# DM1092_Battery_Alarm.net
KiCad netlist of a schematic drawn in Altium Designer
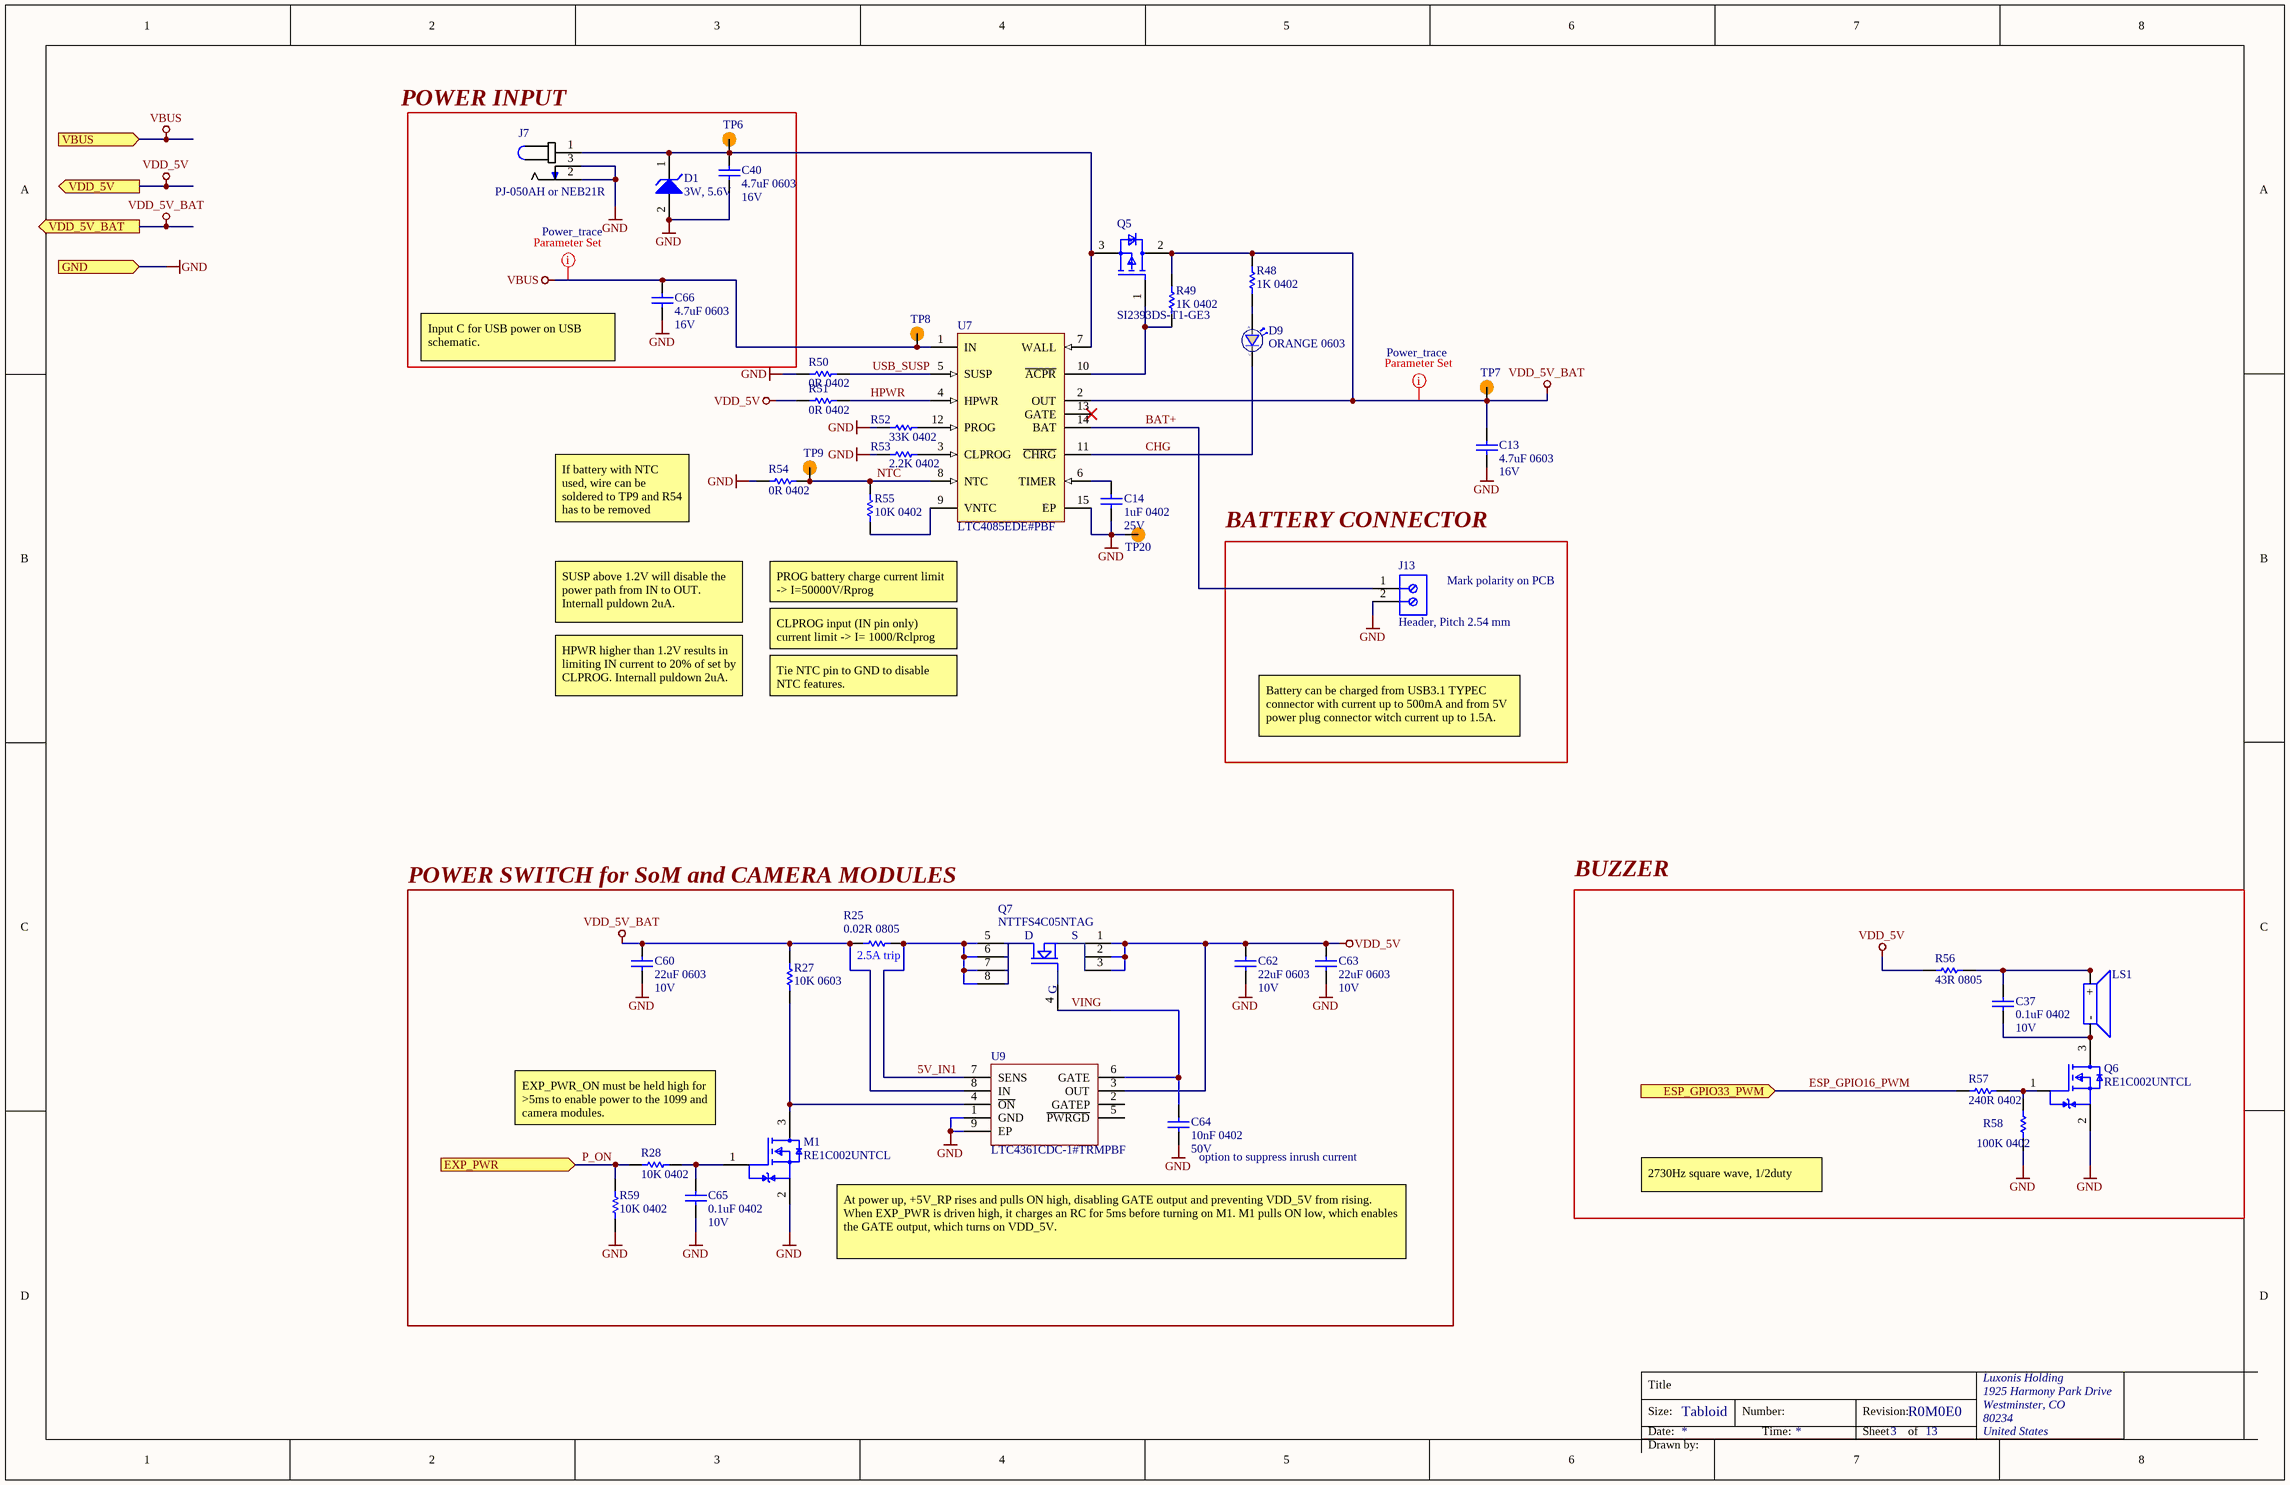
[diagram p0: DM1092_Battery&Alarm.SchDoc]

(export (version "E")
  (design (tool "Eeschema 10.0.6"))
  (components
    (comp (ref "C13")
      (value "4.7uF 0603")
      (footprint "CAP_Altium_Vault_Generic:CAPC0603(1608)100_N")
      (description "CAP CER 4.7UF 16V X5R 0603 10%")
      (fields (field (name "TOLERANCE") "10%") (field (name "VOLTAGE RATING") "16V"))
      (libsource (lib "LuxonisMaster") (part "GRM188R61C475KAAJD"))
    )
    (comp (ref "C14")
      (value "1uF 0402")
      (footprint "CAP_Altium_Vault_Generic:CAPC0402(1005)70_N")
      (description "CAP CER 1UF 25V X5R 0402 10%")
      (fields
        (field (name "TOLERANCE") "10%")
        (field (name "VOLTAGE") "25V")
        (field (name "VOLTAGE RATING") "25V")
      )
      (libsource (lib "LuxonisMaster") (part "GRM155R61E105KA12D"))
    )
    (comp (ref "C37")
      (value "0.1uF 0402")
      (footprint "CAP_Altium_Vault_Generic:CAPC0402(1005)70_N")
      (description "CAP CER 0.1UF 10V X7R 0402 5%")
      (fields (field (name "TOLERANCE") "5%") (field (name "VOLTAGE RATING") "10V"))
      (libsource (lib "LuxonisMaster") (part "GRM155R71A104JA01D"))
    )
    (comp (ref "C40")
      (value "4.7uF 0603")
      (footprint "CAP_Altium_Vault_Generic:CAPC0603(1608)100_N")
      (description "CAP CER 4.7UF 16V X5R 0603 10%")
      (fields (field (name "TOLERANCE") "10%") (field (name "VOLTAGE RATING") "16V"))
      (libsource (lib "LuxonisMaster") (part "GRM188R61C475KAAJD"))
    )
    (comp (ref "C60")
      (value "22uF 0603")
      (footprint "CAP_Altium_Vault_Generic:CAPC0603(1608)100_N")
      (description "CAP CER 22UF 10V X5R 0603 20%")
      (fields (field (name "VOLTAGE RATING") "10V") (field (name "TOLERANCE") "20%"))
      (libsource (lib "LuxonisMaster") (part "GRM188R61A226ME15D"))
    )
    (comp (ref "C62")
      (value "22uF 0603")
      (footprint "CAP_Altium_Vault_Generic:CAPC0603(1608)100_N")
      (description "CAP CER 22UF 10V X5R 0603 20%")
      (fields (field (name "VOLTAGE RATING") "10V") (field (name "TOLERANCE") "20%"))
      (libsource (lib "LuxonisMaster") (part "GRM188R61A226ME15D"))
    )
    (comp (ref "C63")
      (value "22uF 0603")
      (footprint "CAP_Altium_Vault_Generic:CAPC0603(1608)100_N")
      (description "CAP CER 22UF 10V X5R 0603 20%")
      (fields (field (name "VOLTAGE RATING") "10V") (field (name "TOLERANCE") "20%"))
      (libsource (lib "LuxonisMaster") (part "GRM188R61A226ME15D"))
    )
    (comp (ref "C64")
      (value "10nF 0402")
      (footprint "CAP_Altium_Vault_Generic:CAPC0402(1005)60_N")
      (description "CAP CER 10000PF 50V X7R 0402")
      (fields
        (field (name "TOLERANCE") "10%")
        (field (name "VOLTAGE") "25V")
        (field (name "VOLTAGE RATING") "50V")
      )
      (libsource (lib "LuxonisMaster") (part "GRM155R71H103KA88D"))
    )
    (comp (ref "C65")
      (value "0.1uF 0402")
      (footprint "CAP_Altium_Vault_Generic:CAPC0402(1005)70_N")
      (description "CAP CER 0.1UF 10V X7R 0402 5%")
      (fields (field (name "TOLERANCE") "5%") (field (name "VOLTAGE RATING") "10V"))
      (libsource (lib "LuxonisMaster") (part "GRM155R71A104JA01D"))
    )
    (comp (ref "C66")
      (value "4.7uF 0603")
      (footprint "CAP_Altium_Vault_Generic:CAPC0603(1608)100_N")
      (description "CAP CER 4.7UF 16V X5R 0603 10%")
      (fields (field (name "TOLERANCE") "10%") (field (name "VOLTAGE RATING") "16V"))
      (libsource (lib "LuxonisMaster") (part "GRM188R61C475KAAJD"))
    )
    (comp (ref "D1")
      (value "3W, 5.6V")
      (footprint "DM1092_R0M0E0:1SMB5919BT3G")
      (description "DIODE ZENER 5.6V 3W SMB")
      (fields (field (name "TOLERANCE") "5%"))
      (libsource (lib "DM1092_R0M0E0") (part "1SMB5919BT3G"))
    )
    (comp (ref "D9")
      (value "ORANGE 0603")
      (footprint "LuxonisMaster:SML_D1xx8W")
      (description "LED ORANGE DIFFUSED 0603 SMD Orange 605nm LED Indication - Discrete 2.2V 0603 (1608 Metric)")
      (libsource (lib "LuxonisMaster") (part "SML-D12D8WT86"))
    )
    (comp (ref "J7")
      (value "PJ-050AH or NEB21R")
      (footprint "LuxonisMaster:PJ-050AH/NEB21R_COMBO")
      (description "CONN POWER PIN 2 POS RA PTH Barrel jack 2.1mm x 5.5mm combo footprint")
      (libsource (lib "LuxonisMaster") (part "PJ-050AH/NEB21R_COMBO"))
    )
    (comp (ref "J13")
      (value "Header, Pitch 2.54 mm")
      (footprint "PHOE-1725656-2")
      (fields
        (field (name "MANUFACTURER PART NO.") "1725656")
        (field (name "MANUFACTURER") "Phoenix Contact")
        (field (name "VOLTAGE") "125V")
      )
      (libsource (lib "DM1092_R0M0E0") (part "1725656"))
    )
    (comp (ref "LS1")
      (value "KSSGJ4B20")
      (footprint "KSSGJ4B20")
      (description "KINGSTATE - KSSGJ4B20 - MAGNETIC TRANSDUCER, SMD TYPE")
      (libsource (lib "DM1092_R0M0E0") (part "KSSGJ4B20"))
    )
    (comp (ref "M1")
      (value "RE1C002UNTCL")
      (footprint "LuxonisMaster:RE1C002UNTCL")
      (description "MOSFET N-CH 20V 0.2A EMT3")
      (libsource (lib "LuxonisMaster") (part "RE1C002UNTCL"))
    )
    (comp (ref "Q5")
      (value "SI2393DS-T1-GE3")
      (footprint "FP-S-03946-MFG")
      (description "MOSFET P-CH 30V 7.5A SOT23-3")
      (fields
        (field (name "MANUFACTURER") "Vishay Siliconix")
        (field (name "MANUFACTURER PART NUMBER") "SI2307CDS-T1-GE3")
      )
      (libsource (lib "DM1092_R0M0E0") (part "SI2393DS-T1-GE3"))
    )
    (comp (ref "Q6")
      (value "RE1C002UNTCL")
      (footprint "LuxonisMaster:RE1C002UNTCL")
      (description "MOSFET N-CH 20V 0.2A EMT3")
      (libsource (lib "LuxonisMaster") (part "RE1C002UNTCL"))
    )
    (comp (ref "Q7")
      (value "NTTFS4C05NTAG")
      (footprint "LuxonisMaster:NTTFS4C05NTAG")
      (description "MOSFET N-CH 30V 75A U8FL")
      (libsource (lib "LuxonisMaster") (part "NTTFS4C05NTAG"))
    )
    (comp (ref "R25")
      (value "0.02R 0805")
      (footprint "RES_Altium_Vault_Generic:RESC0805(2012)_N")
      (description "RES 0.02 OHM 1% 1/2W 0805")
      (fields (field (name "TOLERANCE") "1%"))
      (libsource (lib "LuxonisMaster") (part "ERJ-6BWFR020V"))
    )
    (comp (ref "R27")
      (value "10K 0603")
      (footprint "RES_Altium_Vault_Generic:RESC0603(1608)_N")
      (description "RES SMD 10K OHM 1% 1/10W 0603")
      (fields (field (name "TOLERANCE") "1%"))
      (libsource (lib "LuxonisMaster") (part "RC0603FR-0710KL"))
    )
    (comp (ref "R28")
      (value "10K 0402")
      (footprint "RES_Altium_Vault_Generic:RESC0402(1005)_L")
      (fields (field (name "TOLERANCE") "1%"))
      (libsource (lib "LuxonisMaster") (part "RC0402FR-1310KL"))
    )
    (comp (ref "R48")
      (value "1K 0402")
      (footprint "RES_Altium_Vault_Generic:RESC0402(1005)_N")
      (fields (field (name "TOLERANCE") "1%"))
      (libsource (lib "LuxonisMaster") (part "RC0402FR-071KL"))
    )
    (comp (ref "R49")
      (value "1K 0402")
      (footprint "RES_Altium_Vault_Generic:RESC0402(1005)_N")
      (fields (field (name "TOLERANCE") "1%"))
      (libsource (lib "LuxonisMaster") (part "RC0402FR-071KL"))
    )
    (comp (ref "R50")
      (value "0R 0402")
      (footprint "RES_Altium_Vault_Generic:RESC0402(1005)_L")
      (description "RES SMD 0 OHM JUMPER 1/16W 0402")
      (fields (field (name "TOLERANCE") "5%"))
      (libsource (lib "LuxonisMaster") (part "CRCW04020000Z0ED"))
    )
    (comp (ref "R51")
      (value "0R 0402")
      (footprint "RES_Altium_Vault_Generic:RESC0402(1005)_L")
      (description "RES SMD 0 OHM JUMPER 1/16W 0402")
      (fields (field (name "TOLERANCE") "5%"))
      (libsource (lib "LuxonisMaster") (part "CRCW04020000Z0ED"))
    )
    (comp (ref "R52")
      (value "33K 0402")
      (footprint "RES_Altium_Vault_Generic:RESC0402(1005)_L")
      (description "RES SMD 33K OHM 1% 1/16W 0402")
      (fields (field (name "TOLERANCE") "1%"))
      (libsource (lib "LuxonisMaster") (part "CRCW040233K0FKED"))
    )
    (comp (ref "R53")
      (value "2.2K 0402")
      (footprint "RES_Altium_Vault_Generic:RESC0402(1005)_N")
      (description "RES SMD 2.2K OHM 1% 1/16W 0402")
      (fields (field (name "TOLERANCE") "1%"))
      (libsource (lib "LuxonisMaster") (part "RC0402FR-072K2L"))
    )
    (comp (ref "R54")
      (value "0R 0402")
      (footprint "RES_Altium_Vault_Generic:RESC0402(1005)_L")
      (description "RES SMD 0 OHM JUMPER 1/16W 0402")
      (fields (field (name "TOLERANCE") "5%"))
      (libsource (lib "LuxonisMaster") (part "CRCW04020000Z0ED"))
    )
    (comp (ref "R55")
      (value "10K 0402")
      (footprint "RES_Altium_Vault_Generic:RESC0402(1005)_N")
      (fields (field (name "TOLERANCE") "1%"))
      (libsource (lib "LuxonisMaster") (part "RC0402FR-1310KL"))
    )
    (comp (ref "R56")
      (value "43R 0805")
      (footprint "RESC0805(2012)_N")
      (description "RES SMD 43 OHM 5% 1/8W 0805")
      (fields
        (field (name "MANUFACTURER") "Yageo")
        (field (name "MANUFACTURER PART NUMBER") "RC0805JR-0743RL")
      )
      (libsource (lib "LuxonisMaster") (part "RC0805JR-0743RL"))
    )
    (comp (ref "R57")
      (value "240R 0402")
      (footprint "RES_Altium_Vault_Generic:RESC0402(1005)_N")
      (description "RES SMD 240 OHM 1% 1/16W 0402")
      (fields (field (name "TOLERANCE") "1%"))
      (libsource (lib "LuxonisMaster") (part "RC0402FR-07240RL"))
    )
    (comp (ref "R58")
      (value "100K 0402")
      (footprint "RES_Altium_Vault_Generic:RESC0402(1005)_L")
      (description "RES SMD 100K OHM 1% 1/16W 0402")
      (fields (field (name "TOLERANCE") "1%"))
      (libsource (lib "LuxonisMaster") (part "RC0402FR-07100KL"))
    )
    (comp (ref "R59")
      (value "10K 0402")
      (footprint "RES_Altium_Vault_Generic:RESC0402(1005)_L")
      (fields (field (name "TOLERANCE") "1%"))
      (libsource (lib "LuxonisMaster") (part "RC0402FR-1310KL"))
    )
    (comp (ref "TP6")
      (value "TP100_200_NS")
      (footprint "LuxonisMaster:TP100_200_NS")
      (libsource (lib "LuxonisMaster") (part "TEST_POINT"))
    )
    (comp (ref "TP7")
      (value "TP100_200_NS")
      (footprint "LuxonisMaster:TP100_200_NS")
      (libsource (lib "LuxonisMaster") (part "TEST_POINT"))
    )
    (comp (ref "TP8")
      (value "TP100_200_NS")
      (footprint "LuxonisMaster:TP100_200_NS")
      (libsource (lib "LuxonisMaster") (part "TEST_POINT"))
    )
    (comp (ref "TP9")
      (value "TP100_200_NS")
      (footprint "LuxonisMaster:TP100_200_NS")
      (libsource (lib "LuxonisMaster") (part "TEST_POINT"))
    )
    (comp (ref "TP20")
      (value "TP100_200_NS")
      (footprint "LuxonisMaster:TP100_200_NS")
      (libsource (lib "LuxonisMaster") (part "TEST_POINT"))
    )
    (comp (ref "U7")
      (value "LTC4085EDE#PBF")
      (footprint "LT-DE-14_V")
      (fields (field (name "MANUFACTURER") "Linear Technology"))
      (libsource (lib "DM1092_R0M0E0") (part "LTC4085EDE#PBF"))
    )
    (comp (ref "U9")
      (value "LTC4361CDC-1#TRMPBF")
      (footprint "LuxonisMaster:LTC4361CDC-1#TRMPBF")
      (description "IC OVERVOLTAGE/CUR PROT 8-DFN Handheld/Mobile Devices PMIC 8-DFN (2x2)")
      (libsource (lib "LuxonisMaster") (part "LTC4361CDC-1#TRMPBF"))
    )
  )
  (nets
    (net (code "1") (name "/5V_IN1") (class "Default")
      (node (ref "Q7") (pin "5") (pinfunction "D_5") (pintype "passive"))
      (node (ref "Q7") (pin "6") (pinfunction "D_6") (pintype "passive"))
      (node (ref "Q7") (pin "7") (pinfunction "D_7") (pintype "passive"))
      (node (ref "Q7") (pin "8") (pinfunction "D_8") (pintype "passive"))
      (node (ref "R25") (pin "2") (pinfunction "2_2") (pintype "passive"))
      (node (ref "U9") (pin "7") (pinfunction "SENS_7") (pintype "passive"))
    )
    (net (code "2") (name "/BAT+") (class "Default")
      (node (ref "J13") (pin "1") (pinfunction "1_1") (pintype "passive"))
      (node (ref "U7") (pin "14") (pinfunction "BAT_14") (pintype "power_in"))
    )
    (net (code "3") (name "/CHG") (class "Default")
      (node (ref "D9") (pin "1") (pinfunction "C_1") (pintype "passive"))
      (node (ref "U7") (pin "11") (pinfunction "~{CHRG}_11") (pintype "tri_state"))
    )
    (net (code "4") (name "/ESP_GPIO16_PWM") (class "Default")
      (node (ref "R57") (pin "1") (pinfunction "1_1") (pintype "passive"))
    )
    (net (code "5") (name "/HPWR") (class "Default")
      (node (ref "R51") (pin "2") (pinfunction "2_2") (pintype "passive"))
      (node (ref "U7") (pin "4") (pinfunction "HPWR_4") (pintype "input"))
    )
    (net (code "6") (name "/NTC") (class "Default")
      (node (ref "R54") (pin "2") (pinfunction "2_2") (pintype "passive"))
      (node (ref "R55") (pin "2") (pinfunction "2_2") (pintype "passive"))
      (node (ref "TP9") (pin "1") (pintype "passive"))
      (node (ref "U7") (pin "8") (pinfunction "NTC_8") (pintype "input"))
    )
    (net (code "7") (name "/P_ON") (class "Default")
      (node (ref "R28") (pin "2") (pinfunction "2_2") (pintype "passive"))
      (node (ref "R59") (pin "2") (pinfunction "2_2") (pintype "passive"))
    )
    (net (code "8") (name "/USB_SUSP") (class "Default")
      (node (ref "R50") (pin "2") (pinfunction "2_2") (pintype "passive"))
      (node (ref "U7") (pin "5") (pinfunction "SUSP_5") (pintype "input"))
    )
    (net (code "9") (name "/VING") (class "Default")
      (node (ref "C64") (pin "2") (pinfunction "2_2") (pintype "passive"))
      (node (ref "Q7") (pin "4") (pinfunction "G_4") (pintype "passive"))
      (node (ref "U9") (pin "6") (pinfunction "GATE_6") (pintype "passive"))
    )
    (net (code "10") (name "GND") (class "Default")
      (node (ref "C13") (pin "1") (pinfunction "1_1") (pintype "passive"))
      (node (ref "C14") (pin "1") (pinfunction "1_1") (pintype "passive"))
      (node (ref "C40") (pin "1") (pinfunction "1_1") (pintype "passive"))
      (node (ref "C60") (pin "1") (pinfunction "1_1") (pintype "passive"))
      (node (ref "C62") (pin "1") (pinfunction "1_1") (pintype "passive"))
      (node (ref "C63") (pin "1") (pinfunction "1_1") (pintype "passive"))
      (node (ref "C64") (pin "1") (pinfunction "1_1") (pintype "passive"))
      (node (ref "C65") (pin "1") (pinfunction "1_1") (pintype "passive"))
      (node (ref "C66") (pin "1") (pinfunction "1_1") (pintype "passive"))
      (node (ref "D1") (pin "2") (pinfunction "A_2") (pintype "passive"))
      (node (ref "J13") (pin "2") (pinfunction "2_2") (pintype "passive"))
      (node (ref "J7") (pin "2") (pinfunction "2_2") (pintype "passive"))
      (node (ref "J7") (pin "3") (pinfunction "3_3") (pintype "passive"))
      (node (ref "M1") (pin "2") (pinfunction "Source_2") (pintype "passive"))
      (node (ref "Q6") (pin "2") (pinfunction "Source_2") (pintype "passive"))
      (node (ref "R50") (pin "1") (pinfunction "1_1") (pintype "passive"))
      (node (ref "R52") (pin "1") (pinfunction "1_1") (pintype "passive"))
      (node (ref "R53") (pin "1") (pinfunction "1_1") (pintype "passive"))
      (node (ref "R54") (pin "1") (pinfunction "1_1") (pintype "passive"))
      (node (ref "R58") (pin "1") (pinfunction "1_1") (pintype "passive"))
      (node (ref "R59") (pin "1") (pinfunction "1_1") (pintype "passive"))
      (node (ref "TP20") (pin "1") (pintype "passive"))
      (node (ref "U7") (pin "15") (pinfunction "EP_15") (pintype "power_in"))
      (node (ref "U9") (pin "1") (pinfunction "GND_1") (pintype "passive"))
      (node (ref "U9") (pin "9") (pinfunction "EP_9") (pintype "passive"))
    )
    (net (code "11") (name "Net-(C37-Pad1)") (class "Default")
      (node (ref "C37") (pin "1") (pinfunction "1_1") (pintype "passive"))
      (node (ref "LS1") (pin "1") (pinfunction "+_1") (pintype "passive"))
      (node (ref "LS1") (pin "4") (pinfunction "+_4") (pintype "passive"))
      (node (ref "R56") (pin "2") (pinfunction "2_2") (pintype "passive"))
    )
    (net (code "12") (name "Net-(D1-K)") (class "Default")
      (node (ref "C40") (pin "2") (pinfunction "2_2") (pintype "passive"))
      (node (ref "D1") (pin "1") (pinfunction "K_1") (pintype "passive"))
      (node (ref "J7") (pin "1") (pinfunction "1_1") (pintype "passive"))
      (node (ref "Q5") (pin "3") (pinfunction "D_3") (pintype "passive"))
      (node (ref "TP6") (pin "1") (pintype "passive"))
      (node (ref "U7") (pin "7") (pinfunction "WALL_7") (pintype "input"))
    )
    (net (code "13") (name "Net-(D9-A)") (class "Default")
      (node (ref "D9") (pin "2") (pinfunction "A_2") (pintype "passive"))
      (node (ref "R48") (pin "1") (pinfunction "1_1") (pintype "passive"))
    )
    (net (code "14") (name "Net-(M1-Drain)") (class "Default")
      (node (ref "M1") (pin "3") (pinfunction "Drain_3") (pintype "passive"))
      (node (ref "R27") (pin "1") (pinfunction "1_1") (pintype "passive"))
      (node (ref "U9") (pin "4") (pinfunction "~{ON}_4") (pintype "passive"))
    )
    (net (code "15") (name "Net-(M1-Gate)") (class "Default")
      (node (ref "C65") (pin "2") (pinfunction "2_2") (pintype "passive"))
      (node (ref "M1") (pin "1") (pinfunction "Gate_1") (pintype "passive"))
      (node (ref "R28") (pin "1") (pinfunction "1_1") (pintype "passive"))
    )
    (net (code "16") (name "Net-(Q5-G)") (class "Default")
      (node (ref "Q5") (pin "1") (pinfunction "G_1") (pintype "passive"))
      (node (ref "R49") (pin "1") (pinfunction "1_1") (pintype "passive"))
      (node (ref "U7") (pin "10") (pinfunction "~{ACPR}_10") (pintype "tri_state"))
    )
    (net (code "17") (name "Net-(Q6-Drain)") (class "Default")
      (node (ref "C37") (pin "2") (pinfunction "2_2") (pintype "passive"))
      (node (ref "LS1") (pin "2") (pinfunction "-_2") (pintype "passive"))
      (node (ref "LS1") (pin "3") (pinfunction "-_3") (pintype "passive"))
      (node (ref "Q6") (pin "3") (pinfunction "Drain_3") (pintype "passive"))
    )
    (net (code "18") (name "Net-(Q6-Gate)") (class "Default")
      (node (ref "Q6") (pin "1") (pinfunction "Gate_1") (pintype "passive"))
      (node (ref "R57") (pin "2") (pinfunction "2_2") (pintype "passive"))
      (node (ref "R58") (pin "2") (pinfunction "2_2") (pintype "passive"))
    )
    (net (code "19") (name "Net-(U7-CLPROG)") (class "Default")
      (node (ref "R53") (pin "2") (pinfunction "2_2") (pintype "passive"))
      (node (ref "U7") (pin "3") (pinfunction "CLPROG_3") (pintype "input"))
    )
    (net (code "20") (name "Net-(U7-PROG)") (class "Default")
      (node (ref "R52") (pin "2") (pinfunction "2_2") (pintype "passive"))
      (node (ref "U7") (pin "12") (pinfunction "PROG_12") (pintype "input"))
    )
    (net (code "21") (name "Net-(U7-TIMER)") (class "Default")
      (node (ref "C14") (pin "2") (pinfunction "2_2") (pintype "passive"))
      (node (ref "U7") (pin "6") (pinfunction "TIMER_6") (pintype "input"))
    )
    (net (code "22") (name "Net-(U7-VNTC)") (class "Default")
      (node (ref "R55") (pin "1") (pinfunction "1_1") (pintype "passive"))
      (node (ref "U7") (pin "9") (pinfunction "VNTC_9") (pintype "passive"))
    )
    (net (code "23") (name "VBUS") (class "Default")
      (node (ref "C66") (pin "2") (pinfunction "2_2") (pintype "passive"))
      (node (ref "TP8") (pin "1") (pintype "passive"))
      (node (ref "U7") (pin "1") (pinfunction "IN_1") (pintype "power_in"))
    )
    (net (code "24") (name "VDD_5V") (class "Default")
      (node (ref "C62") (pin "2") (pinfunction "2_2") (pintype "passive"))
      (node (ref "C63") (pin "2") (pinfunction "2_2") (pintype "passive"))
      (node (ref "Q7") (pin "1") (pinfunction "S_1") (pintype "passive"))
      (node (ref "Q7") (pin "2") (pinfunction "S_2") (pintype "passive"))
      (node (ref "Q7") (pin "3") (pinfunction "S_3") (pintype "passive"))
      (node (ref "R51") (pin "1") (pinfunction "1_1") (pintype "passive"))
      (node (ref "R56") (pin "1") (pinfunction "1_1") (pintype "passive"))
      (node (ref "U9") (pin "3") (pinfunction "OUT_3") (pintype "passive"))
    )
    (net (code "25") (name "VDD_5V_BAT") (class "Default")
      (node (ref "C13") (pin "2") (pinfunction "2_2") (pintype "passive"))
      (node (ref "C60") (pin "2") (pinfunction "2_2") (pintype "passive"))
      (node (ref "Q5") (pin "2") (pinfunction "S_2") (pintype "passive"))
      (node (ref "R25") (pin "1") (pinfunction "1_1") (pintype "passive"))
      (node (ref "R27") (pin "2") (pinfunction "2_2") (pintype "passive"))
      (node (ref "R48") (pin "2") (pinfunction "2_2") (pintype "passive"))
      (node (ref "R49") (pin "2") (pinfunction "2_2") (pintype "passive"))
      (node (ref "TP7") (pin "1") (pintype "passive"))
      (node (ref "U7") (pin "2") (pinfunction "OUT_2") (pintype "power_in"))
      (node (ref "U9") (pin "8") (pinfunction "IN_8") (pintype "passive"))
    )
    (net (code "26") (name "unconnected-(U7-GATE-Pad13)") (class "Default")
      (node (ref "U7") (pin "13") (pinfunction "GATE_13") (pintype "tri_state+no_connect"))
    )
    (net (code "27") (name "unconnected-(U9-GATEP-Pad2)") (class "Default")
      (node (ref "U9") (pin "2") (pinfunction "GATEP_2") (pintype "passive"))
    )
    (net (code "28") (name "unconnected-(U9-~{PWRGD}-Pad5)") (class "Default")
      (node (ref "U9") (pin "5") (pinfunction "~{PWRGD}_5") (pintype "passive"))
    )
  )
)
